# Pineapple_1_TM2013B.net
KiCad netlist of a schematic drawn in EAGLE
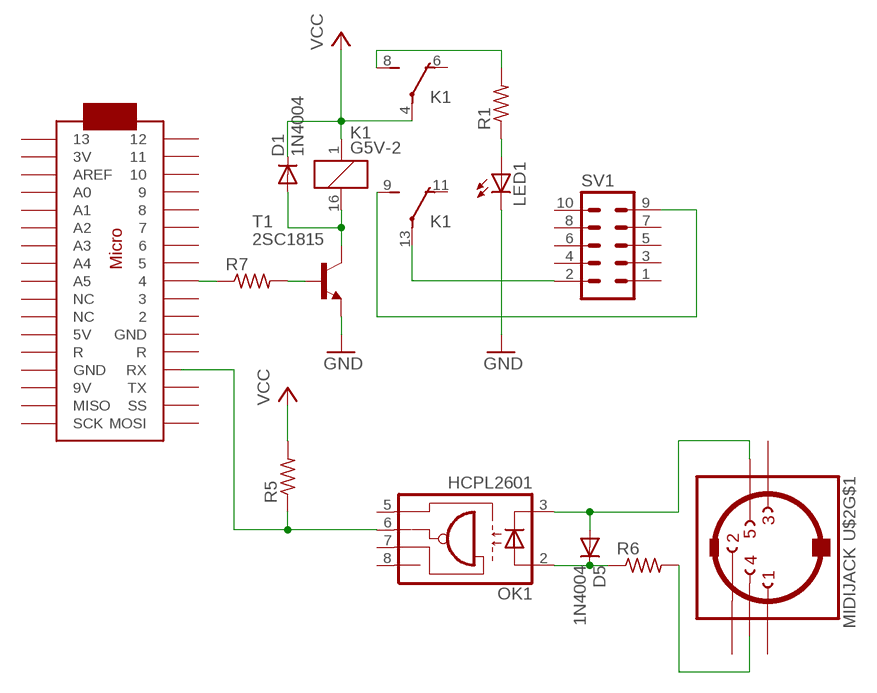
[diagram p0: schematic, sheet 1]

(export (version "E")
  (design (tool "Eeschema 10.0.6"))
  (components
    (comp (ref "D1")
      (value "1N4004")
      (footprint "eagle-import:DO41-10")
      (libsource (lib "eagle-import") (part "1N4004"))
    )
    (comp (ref "D5")
      (value "1N4004")
      (footprint "eagle-import:DO41-10")
      (libsource (lib "eagle-import") (part "1N4004"))
    )
    (comp (ref "K1")
      (value "G5V-2")
      (footprint "eagle-import:G5V-2")
      (fields (field (name "MPN") "G5V-2 5DC"))
      (libsource (lib "eagle-import") (part "G5V-2"))
    )
    (comp (ref "LED1")
      (value "LED3MM")
      (footprint "eagle-import:LED3MM")
      (libsource (lib "eagle-import") (part "LED3MM"))
    )
    (comp (ref "OK1")
      (value "HCPL2601")
      (footprint "eagle-import:DIL08")
      (fields (field (name "MF") "AGILENT TECHNOLOGIES") (field (name "MPN") "HCPL-2601-000E"))
      (libsource (lib "eagle-import") (part "HCPL2601"))
    )
    (comp (ref "R1")
      (value "R-US_0204/5")
      (footprint "eagle-import:0204_5")
      (libsource (lib "eagle-import") (part "R-US_0204/5"))
    )
    (comp (ref "R5")
      (value "R-US_0204/5")
      (footprint "eagle-import:0204_5")
      (libsource (lib "eagle-import") (part "R-US_0204/5"))
    )
    (comp (ref "R6")
      (value "R-US_0204/5")
      (footprint "eagle-import:0204_5")
      (libsource (lib "eagle-import") (part "R-US_0204/5"))
    )
    (comp (ref "R7")
      (value "R-US_0204/5")
      (footprint "eagle-import:0204_5")
      (libsource (lib "eagle-import") (part "R-US_0204/5"))
    )
    (comp (ref "SV1")
      (value "ML10L")
      (footprint "eagle-import:ML10L")
      (libsource (lib "eagle-import") (part "ML10L"))
    )
    (comp (ref "T1")
      (value "2SC1815")
      (footprint "eagle-import:TO92-ECB")
      (libsource (lib "eagle-import") (part "2SC1815"))
    )
    (comp (ref "U$1")
      (value "ARDUINOMICRO")
      (footprint "eagle-import:ARDUINOMICRO")
      (libsource (lib "eagle-import") (part "ARDUINOMICRO"))
    )
    (comp (ref "U$2")
      (value "MIDIJACK")
      (footprint "eagle-import:CP-2350")
      (libsource (lib "eagle-import") (part "MIDIJACK"))
    )
  )
  (nets
    (net (code "1") (name "GND") (class "Default")
      (node (ref "LED1") (pin "K") (pinfunction "C_K") (pintype "passive"))
      (node (ref "T1") (pin "E") (pinfunction "E_E") (pintype "passive"))
    )
    (net (code "2") (name "Net-(K1A-S)") (class "Default")
      (node (ref "K1") (pin "8") (pinfunction "S_8") (pintype "passive"))
      (node (ref "R1") (pin "2") (pinfunction "2_2") (pintype "passive"))
    )
    (net (code "3") (name "Net-(K1B-P)") (class "Default")
      (node (ref "K1") (pin "13") (pinfunction "P_13") (pintype "passive"))
      (node (ref "SV1") (pin "2") (pinfunction "2_2") (pintype "passive"))
    )
    (net (code "4") (name "Net-(K1B-S)") (class "Default")
      (node (ref "K1") (pin "9") (pinfunction "S_9") (pintype "passive"))
      (node (ref "SV1") (pin "9") (pinfunction "9_9") (pintype "passive"))
    )
    (net (code "5") (name "Net-(K1C-2)") (class "Default")
      (node (ref "D1") (pin "A") (pinfunction "A_A") (pintype "passive"))
      (node (ref "K1") (pin "16") (pinfunction "2_16") (pintype "passive"))
      (node (ref "T1") (pin "C") (pinfunction "C_C") (pintype "passive"))
    )
    (net (code "6") (name "Net-(LED1-PadA)") (class "Default")
      (node (ref "LED1") (pin "A") (pinfunction "A_A") (pintype "passive"))
      (node (ref "R1") (pin "1") (pinfunction "1_1") (pintype "passive"))
    )
    (net (code "7") (name "Net-(OK1-A)") (class "Default")
      (node (ref "D5") (pin "C") (pinfunction "C_C") (pintype "passive"))
      (node (ref "OK1") (pin "2") (pinfunction "A_2") (pintype "passive"))
      (node (ref "R6") (pin "1") (pinfunction "1_1") (pintype "passive"))
    )
    (net (code "8") (name "Net-(OK1-C)") (class "Default")
      (node (ref "D5") (pin "A") (pinfunction "A_A") (pintype "passive"))
      (node (ref "OK1") (pin "3") (pinfunction "C_3") (pintype "passive"))
      (node (ref "U$2") (pin "5") (pinfunction "5_5") (pintype "passive"))
    )
    (net (code "9") (name "Net-(OK1-OUT)") (class "Default")
      (node (ref "OK1") (pin "6") (pinfunction "OUT_6") (pintype "passive"))
      (node (ref "R5") (pin "1") (pinfunction "1_1") (pintype "passive"))
    )
    (net (code "10") (name "Net-(R6-Pad2)") (class "Default")
      (node (ref "R6") (pin "2") (pinfunction "2_2") (pintype "passive"))
      (node (ref "U$2") (pin "4") (pinfunction "4_4") (pintype "passive"))
    )
    (net (code "11") (name "Net-(R7-Pad2)") (class "Default")
      (node (ref "R7") (pin "2") (pinfunction "2_2") (pintype "passive"))
      (node (ref "T1") (pin "B") (pinfunction "B_B") (pintype "passive"))
    )
    (net (code "12") (name "Net-(U$1-4)") (class "Default")
      (node (ref "R7") (pin "1") (pinfunction "1_1") (pintype "passive"))
      (node (ref "U$1") (pin "P$9") (pinfunction "4_P$9") (pintype "bidirectional"))
    )
    (net (code "13") (name "VCC") (class "Default")
      (node (ref "D1") (pin "C") (pinfunction "C_C") (pintype "passive"))
      (node (ref "K1") (pin "1") (pinfunction "1_1") (pintype "passive"))
      (node (ref "K1") (pin "4") (pinfunction "P_4") (pintype "passive"))
      (node (ref "R5") (pin "2") (pinfunction "2_2") (pintype "passive"))
    )
    (net (code "14") (name "unconnected-(K1A-O-Pad6)") (class "Default")
      (node (ref "K1") (pin "6") (pinfunction "O_6") (pintype "passive"))
    )
    (net (code "15") (name "unconnected-(K1B-O-Pad11)") (class "Default")
      (node (ref "K1") (pin "11") (pinfunction "O_11") (pintype "passive"))
    )
    (net (code "16") (name "unconnected-(OK1-EN-Pad7)") (class "Default")
      (node (ref "OK1") (pin "7") (pinfunction "EN_7") (pintype "passive"))
    )
    (net (code "17") (name "unconnected-(OK1-GND-Pad5)") (class "Default")
      (node (ref "OK1") (pin "5") (pinfunction "GND_5") (pintype "passive"))
    )
    (net (code "18") (name "unconnected-(OK1-VCC-Pad8)") (class "Default")
      (node (ref "OK1") (pin "8") (pinfunction "VCC_8") (pintype "passive"))
    )
    (net (code "19") (name "unconnected-(SV1-Pad1)") (class "Default")
      (node (ref "SV1") (pin "1") (pinfunction "1_1") (pintype "passive"))
    )
    (net (code "20") (name "unconnected-(SV1-Pad3)") (class "Default")
      (node (ref "SV1") (pin "3") (pinfunction "3_3") (pintype "passive"))
    )
    (net (code "21") (name "unconnected-(SV1-Pad4)") (class "Default")
      (node (ref "SV1") (pin "4") (pinfunction "4_4") (pintype "passive"))
    )
    (net (code "22") (name "unconnected-(SV1-Pad5)") (class "Default")
      (node (ref "SV1") (pin "5") (pinfunction "5_5") (pintype "passive"))
    )
    (net (code "23") (name "unconnected-(SV1-Pad6)") (class "Default")
      (node (ref "SV1") (pin "6") (pinfunction "6_6") (pintype "passive"))
    )
    (net (code "24") (name "unconnected-(SV1-Pad7)") (class "Default")
      (node (ref "SV1") (pin "7") (pinfunction "7_7") (pintype "passive"))
    )
    (net (code "25") (name "unconnected-(SV1-Pad8)") (class "Default")
      (node (ref "SV1") (pin "8") (pinfunction "8_8") (pintype "passive"))
    )
    (net (code "26") (name "unconnected-(SV1-Pad10)") (class "Default")
      (node (ref "SV1") (pin "10") (pinfunction "10_10") (pintype "passive"))
    )
    (net (code "27") (name "unconnected-(U$1-2-PadP$11)") (class "Default")
      (node (ref "U$1") (pin "P$11") (pinfunction "2_P$11") (pintype "bidirectional"))
    )
    (net (code "28") (name "unconnected-(U$1-3-PadP$10)") (class "Default")
      (node (ref "U$1") (pin "P$10") (pinfunction "3_P$10") (pintype "bidirectional"))
    )
    (net (code "29") (name "unconnected-(U$1-3V-PadP$33)") (class "Default")
      (node (ref "U$1") (pin "P$33") (pinfunction "3V_P$33") (pintype "bidirectional"))
    )
    (net (code "30") (name "unconnected-(U$1-5-PadP$8)") (class "Default")
      (node (ref "U$1") (pin "P$8") (pinfunction "5_P$8") (pintype "bidirectional"))
    )
    (net (code "31") (name "unconnected-(U$1-5V-PadP$23)") (class "Default")
      (node (ref "U$1") (pin "P$23") (pinfunction "5V_P$23") (pintype "bidirectional"))
    )
    (net (code "32") (name "unconnected-(U$1-6-PadP$7)") (class "Default")
      (node (ref "U$1") (pin "P$7") (pinfunction "6_P$7") (pintype "bidirectional"))
    )
    (net (code "33") (name "unconnected-(U$1-7-PadP$6)") (class "Default")
      (node (ref "U$1") (pin "P$6") (pinfunction "7_P$6") (pintype "bidirectional"))
    )
    (net (code "34") (name "unconnected-(U$1-8-PadP$5)") (class "Default")
      (node (ref "U$1") (pin "P$5") (pinfunction "8_P$5") (pintype "bidirectional"))
    )
    (net (code "35") (name "unconnected-(U$1-9-PadP$4)") (class "Default")
      (node (ref "U$1") (pin "P$4") (pinfunction "9_P$4") (pintype "bidirectional"))
    )
    (net (code "36") (name "unconnected-(U$1-9V-PadP$20)") (class "Default")
      (node (ref "U$1") (pin "P$20") (pinfunction "9V_P$20") (pintype "bidirectional"))
    )
    (net (code "37") (name "unconnected-(U$1-10-PadP$3)") (class "Default")
      (node (ref "U$1") (pin "P$3") (pinfunction "10_P$3") (pintype "bidirectional"))
    )
    (net (code "38") (name "unconnected-(U$1-11-PadP$2)") (class "Default")
      (node (ref "U$1") (pin "P$2") (pinfunction "11_P$2") (pintype "bidirectional"))
    )
    (net (code "39") (name "unconnected-(U$1-12-PadP$1)") (class "Default")
      (node (ref "U$1") (pin "P$1") (pinfunction "12_P$1") (pintype "bidirectional"))
    )
    (net (code "40") (name "unconnected-(U$1-13-PadP$34)") (class "Default")
      (node (ref "U$1") (pin "P$34") (pinfunction "13_P$34") (pintype "bidirectional"))
    )
    (net (code "41") (name "unconnected-(U$1-A0-PadP$31)") (class "Default")
      (node (ref "U$1") (pin "P$31") (pinfunction "A0_P$31") (pintype "bidirectional"))
    )
    (net (code "42") (name "unconnected-(U$1-A1-PadP$30)") (class "Default")
      (node (ref "U$1") (pin "P$30") (pinfunction "A1_P$30") (pintype "bidirectional"))
    )
    (net (code "43") (name "unconnected-(U$1-A2-PadP$29)") (class "Default")
      (node (ref "U$1") (pin "P$29") (pinfunction "A2_P$29") (pintype "bidirectional"))
    )
    (net (code "44") (name "unconnected-(U$1-A3-PadP$28)") (class "Default")
      (node (ref "U$1") (pin "P$28") (pinfunction "A3_P$28") (pintype "bidirectional"))
    )
    (net (code "45") (name "unconnected-(U$1-A4-PadP$27)") (class "Default")
      (node (ref "U$1") (pin "P$27") (pinfunction "A4_P$27") (pintype "bidirectional"))
    )
    (net (code "46") (name "unconnected-(U$1-A5-PadP$26)") (class "Default")
      (node (ref "U$1") (pin "P$26") (pinfunction "A5_P$26") (pintype "bidirectional"))
    )
    (net (code "47") (name "unconnected-(U$1-AREF-PadP$32)") (class "Default")
      (node (ref "U$1") (pin "P$32") (pinfunction "AREF_P$32") (pintype "bidirectional"))
    )
    (net (code "48") (name "unconnected-(U$1-GND-PadP$12)") (class "Default")
      (node (ref "U$1") (pin "P$12") (pinfunction "GND_P$12") (pintype "bidirectional"))
    )
    (net (code "49") (name "unconnected-(U$1-GND-PadP$21)") (class "Default")
      (node (ref "U$1") (pin "P$21") (pinfunction "GND_P$21") (pintype "bidirectional"))
    )
    (net (code "50") (name "unconnected-(U$1-MISO-PadP$19)") (class "Default")
      (node (ref "U$1") (pin "P$19") (pinfunction "MISO_P$19") (pintype "bidirectional"))
    )
    (net (code "51") (name "unconnected-(U$1-MOSI-PadP$17)") (class "Default")
      (node (ref "U$1") (pin "P$17") (pinfunction "MOSI_P$17") (pintype "bidirectional"))
    )
    (net (code "52") (name "unconnected-(U$1-NC-PadP$24)") (class "Default")
      (node (ref "U$1") (pin "P$24") (pinfunction "NC_P$24") (pintype "bidirectional"))
    )
    (net (code "53") (name "unconnected-(U$1-NC-PadP$25)") (class "Default")
      (node (ref "U$1") (pin "P$25") (pinfunction "NC_P$25") (pintype "bidirectional"))
    )
    (net (code "54") (name "unconnected-(U$1-R-PadP$13)") (class "Default")
      (node (ref "U$1") (pin "P$13") (pinfunction "R_P$13") (pintype "bidirectional"))
    )
    (net (code "55") (name "unconnected-(U$1-R-PadP$22)") (class "Default")
      (node (ref "U$1") (pin "P$22") (pinfunction "R_P$22") (pintype "bidirectional"))
    )
    (net (code "56") (name "unconnected-(U$1-RX-PadP$14)") (class "Default")
      (node (ref "U$1") (pin "P$14") (pinfunction "RX_P$14") (pintype "bidirectional"))
    )
    (net (code "57") (name "unconnected-(U$1-SCK-PadP$18)") (class "Default")
      (node (ref "U$1") (pin "P$18") (pinfunction "SCK_P$18") (pintype "bidirectional"))
    )
    (net (code "58") (name "unconnected-(U$1-SS-PadP$16)") (class "Default")
      (node (ref "U$1") (pin "P$16") (pinfunction "SS_P$16") (pintype "bidirectional"))
    )
    (net (code "59") (name "unconnected-(U$1-TX-PadP$15)") (class "Default")
      (node (ref "U$1") (pin "P$15") (pinfunction "TX_P$15") (pintype "bidirectional"))
    )
    (net (code "60") (name "unconnected-(U$2-Pad1)") (class "Default")
      (node (ref "U$2") (pin "1") (pinfunction "1_1") (pintype "passive"))
    )
    (net (code "61") (name "unconnected-(U$2-Pad2)") (class "Default")
      (node (ref "U$2") (pin "2") (pinfunction "2_2") (pintype "passive"))
    )
    (net (code "62") (name "unconnected-(U$2-Pad3)") (class "Default")
      (node (ref "U$2") (pin "3") (pinfunction "3_3") (pintype "passive"))
    )
  )
)
